# mainboard_wifi_v1_0.net
KiCad netlist of a schematic drawn in Altium Designer
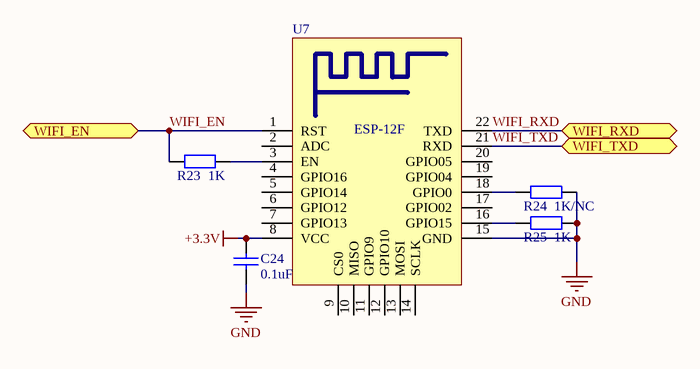
[diagram p0: mainboard_wifi.v1.0.SchDoc]

(export (version "E")
  (design (tool "Eeschema 10.0.6"))
  (components
    (comp (ref "C24")
      (value "0.1uF")
      (footprint "0805")
      (description "Capacitor")
      (libsource (lib "Miscellaneous Devices") (part "Cap"))
    )
    (comp (ref "R23")
      (value "1K")
      (footprint "0805")
      (description "Resistor")
      (libsource (lib "Miscellaneous Devices") (part "Res2"))
    )
    (comp (ref "R24")
      (value "1K/NC")
      (footprint "0805")
      (description "Resistor")
      (libsource (lib "Miscellaneous Devices") (part "Res2"))
    )
    (comp (ref "R25")
      (value "1K")
      (footprint "0805")
      (description "Resistor")
      (libsource (lib "Miscellaneous Devices") (part "Res2"))
    )
    (comp (ref "U7") (value "ESP-12F") (footprint "ESP-12F") (libsource (lib "Componet") (part "ESP-12F")))
  )
  (nets
    (net (code "1") (name "+3.3V") (class "Default")
      (node (ref "C24") (pin "2") (pinfunction "2_2") (pintype "passive"))
      (node (ref "U7") (pin "8") (pinfunction "VCC_8") (pintype "passive"))
    )
    (net (code "2") (name "/WIFI_EN") (class "Default")
      (node (ref "R23") (pin "1") (pinfunction "1_1") (pintype "passive"))
      (node (ref "U7") (pin "1") (pinfunction "RST_1") (pintype "passive"))
    )
    (net (code "3") (name "/WIFI_RXD") (class "Default")
      (node (ref "U7") (pin "22") (pinfunction "TXD_22") (pintype "passive"))
    )
    (net (code "4") (name "/WIFI_TXD") (class "Default")
      (node (ref "U7") (pin "21") (pinfunction "RXD_21") (pintype "passive"))
    )
    (net (code "5") (name "GND") (class "Default")
      (node (ref "C24") (pin "1") (pinfunction "1_1") (pintype "passive"))
      (node (ref "R24") (pin "2") (pinfunction "2_2") (pintype "passive"))
      (node (ref "R25") (pin "2") (pinfunction "2_2") (pintype "passive"))
      (node (ref "U7") (pin "15") (pinfunction "GND_15") (pintype "passive"))
    )
    (net (code "6") (name "Net-(U7-EN)") (class "Default")
      (node (ref "R23") (pin "2") (pinfunction "2_2") (pintype "passive"))
      (node (ref "U7") (pin "3") (pinfunction "EN_3") (pintype "passive"))
    )
    (net (code "7") (name "Net-(U7-GPIO0)") (class "Default")
      (node (ref "R24") (pin "1") (pinfunction "1_1") (pintype "passive"))
      (node (ref "U7") (pin "18") (pinfunction "GPIO0_18") (pintype "passive"))
    )
    (net (code "8") (name "Net-(U7-GPIO15)") (class "Default")
      (node (ref "R25") (pin "1") (pinfunction "1_1") (pintype "passive"))
      (node (ref "U7") (pin "16") (pinfunction "GPIO15_16") (pintype "passive"))
    )
    (net (code "9") (name "unconnected-(U7-ADC-Pad2)") (class "Default")
      (node (ref "U7") (pin "2") (pinfunction "ADC_2") (pintype "passive"))
    )
    (net (code "10") (name "unconnected-(U7-CS0-Pad9)") (class "Default")
      (node (ref "U7") (pin "9") (pinfunction "CS0_9") (pintype "passive"))
    )
    (net (code "11") (name "unconnected-(U7-GPIO02-Pad17)") (class "Default")
      (node (ref "U7") (pin "17") (pinfunction "GPIO02_17") (pintype "passive"))
    )
    (net (code "12") (name "unconnected-(U7-GPIO04-Pad19)") (class "Default")
      (node (ref "U7") (pin "19") (pinfunction "GPIO04_19") (pintype "passive"))
    )
    (net (code "13") (name "unconnected-(U7-GPIO05-Pad20)") (class "Default")
      (node (ref "U7") (pin "20") (pinfunction "GPIO05_20") (pintype "passive"))
    )
    (net (code "14") (name "unconnected-(U7-GPIO9-Pad11)") (class "Default")
      (node (ref "U7") (pin "11") (pinfunction "GPIO9_11") (pintype "passive"))
    )
    (net (code "15") (name "unconnected-(U7-GPIO10-Pad12)") (class "Default")
      (node (ref "U7") (pin "12") (pinfunction "GPIO10_12") (pintype "passive"))
    )
    (net (code "16") (name "unconnected-(U7-GPIO12-Pad6)") (class "Default")
      (node (ref "U7") (pin "6") (pinfunction "GPIO12_6") (pintype "passive"))
    )
    (net (code "17") (name "unconnected-(U7-GPIO13-Pad7)") (class "Default")
      (node (ref "U7") (pin "7") (pinfunction "GPIO13_7") (pintype "passive"))
    )
    (net (code "18") (name "unconnected-(U7-GPIO14-Pad5)") (class "Default")
      (node (ref "U7") (pin "5") (pinfunction "GPIO14_5") (pintype "passive"))
    )
    (net (code "19") (name "unconnected-(U7-GPIO16-Pad4)") (class "Default")
      (node (ref "U7") (pin "4") (pinfunction "GPIO16_4") (pintype "passive"))
    )
    (net (code "20") (name "unconnected-(U7-MISO-Pad10)") (class "Default")
      (node (ref "U7") (pin "10") (pinfunction "MISO_10") (pintype "passive"))
    )
    (net (code "21") (name "unconnected-(U7-MOSI-Pad13)") (class "Default")
      (node (ref "U7") (pin "13") (pinfunction "MOSI_13") (pintype "passive"))
    )
    (net (code "22") (name "unconnected-(U7-SCLK-Pad14)") (class "Default")
      (node (ref "U7") (pin "14") (pinfunction "SCLK_14") (pintype "passive"))
    )
  )
)
